# Sheet1.net
KiCad netlist of a schematic drawn in Altium Designer
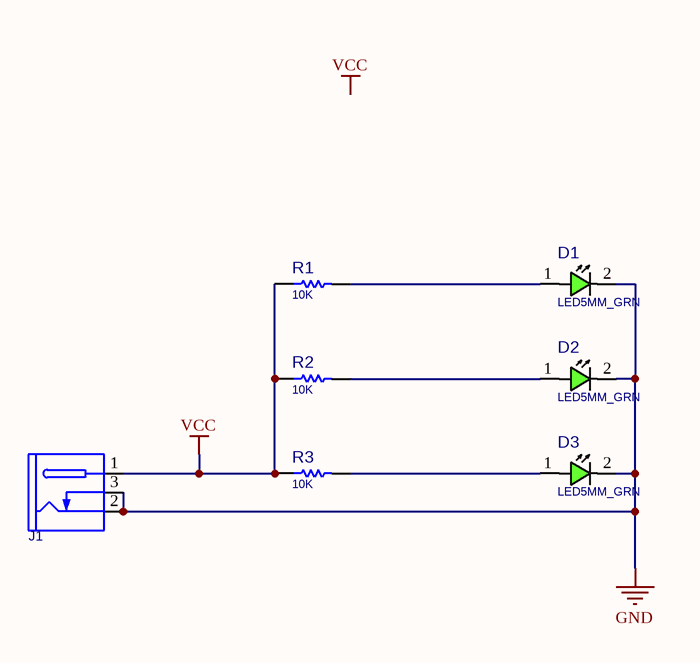
[diagram p0: Sheet1.SchDoc]

(export (version "E")
  (design (tool "Eeschema 10.0.6"))
  (components
    (comp (ref "D1")
      (value "LED5MM_GRN")
      (footprint "LED5MM_GRN")
      (description "LED, THD, 5MM, GREEN")
      (fields (field (name "MANF") "MANF") (field (name "MANF_P#") "MANF_PART#"))
      (libsource (lib "led(diode)") (part "LED_THD_5MM_GRN"))
    )
    (comp (ref "D2")
      (value "LED5MM_GRN")
      (footprint "LED5MM_GRN")
      (description "LED, THD, 5MM, GREEN")
      (fields (field (name "MANF") "MANF") (field (name "MANF_P#") "MANF_PART#"))
      (libsource (lib "led(diode)") (part "LED_THD_5MM_GRN"))
    )
    (comp (ref "D3")
      (value "LED5MM_GRN")
      (footprint "LED5MM_GRN")
      (description "LED, THD, 5MM, GREEN")
      (fields (field (name "MANF") "MANF") (field (name "MANF_P#") "MANF_PART#"))
      (libsource (lib "led(diode)") (part "LED_THD_5MM_GRN"))
    )
    (comp (ref "J1")
      (value "DC_POWER_JACK")
      (footprint "JAC_PWR1")
      (description "CONN, PWR JACK DC, PLUG DIAM 1.0MM RA THD")
      (fields (field (name "MANF") "CUI STACK") (field (name "MANF_P#") "PJ-031CH, PJ-031C"))
      (libsource (lib "conn_powerJack") (part "CONN_PWR_JACKR1"))
    )
    (comp (ref "R1")
      (value "10K")
      (footprint "R025W_AX04")
      (description "RESISTOR, THD")
      (fields (field (name "MANF_P#") "RK73H1ETTP4701F") (field (name "MANF") "KOA SPEER"))
      (libsource (lib "passive_thd") (part "RES_THD"))
    )
    (comp (ref "R2")
      (value "10K")
      (footprint "R025W_AX04")
      (description "RESISTOR, THD")
      (fields (field (name "MANF_P#") "RK73H1ETTP4701F") (field (name "MANF") "KOA SPEER"))
      (libsource (lib "passive_thd") (part "RES_THD"))
    )
    (comp (ref "R3")
      (value "10K")
      (footprint "R025W_AX04")
      (description "RESISTOR, THD")
      (fields (field (name "MANF_P#") "RK73H1ETTP4701F") (field (name "MANF") "KOA SPEER"))
      (libsource (lib "passive_thd") (part "RES_THD"))
    )
  )
  (nets
    (net (code "1") (name "GND") (class "Default")
      (node (ref "D1") (pin "2") (pinfunction "CATHODE_2") (pintype "passive"))
      (node (ref "D2") (pin "2") (pinfunction "CATHODE_2") (pintype "passive"))
      (node (ref "D3") (pin "2") (pinfunction "CATHODE_2") (pintype "passive"))
      (node (ref "J1") (pin "2") (pinfunction "SLEEVE_2") (pintype "power_in"))
      (node (ref "J1") (pin "3") (pinfunction "INSERTION_DET_3") (pintype "power_in"))
    )
    (net (code "2") (name "Net-(D1-ANODE)") (class "Default")
      (node (ref "D1") (pin "1") (pinfunction "ANODE_1") (pintype "passive"))
      (node (ref "R1") (pin "2") (pinfunction "2_2") (pintype "passive"))
    )
    (net (code "3") (name "Net-(D2-ANODE)") (class "Default")
      (node (ref "D2") (pin "1") (pinfunction "ANODE_1") (pintype "passive"))
      (node (ref "R2") (pin "2") (pinfunction "2_2") (pintype "passive"))
    )
    (net (code "4") (name "Net-(D3-ANODE)") (class "Default")
      (node (ref "D3") (pin "1") (pinfunction "ANODE_1") (pintype "passive"))
      (node (ref "R3") (pin "2") (pinfunction "2_2") (pintype "passive"))
    )
    (net (code "5") (name "VCC") (class "Default")
      (node (ref "J1") (pin "1") (pinfunction "TIP_1") (pintype "power_in"))
      (node (ref "R1") (pin "1") (pinfunction "1_1") (pintype "passive"))
      (node (ref "R2") (pin "1") (pinfunction "1_1") (pintype "passive"))
      (node (ref "R3") (pin "1") (pinfunction "1_1") (pintype "passive"))
    )
  )
)
